# Main_BoardV1.net
KiCad netlist of a schematic drawn in EAGLE
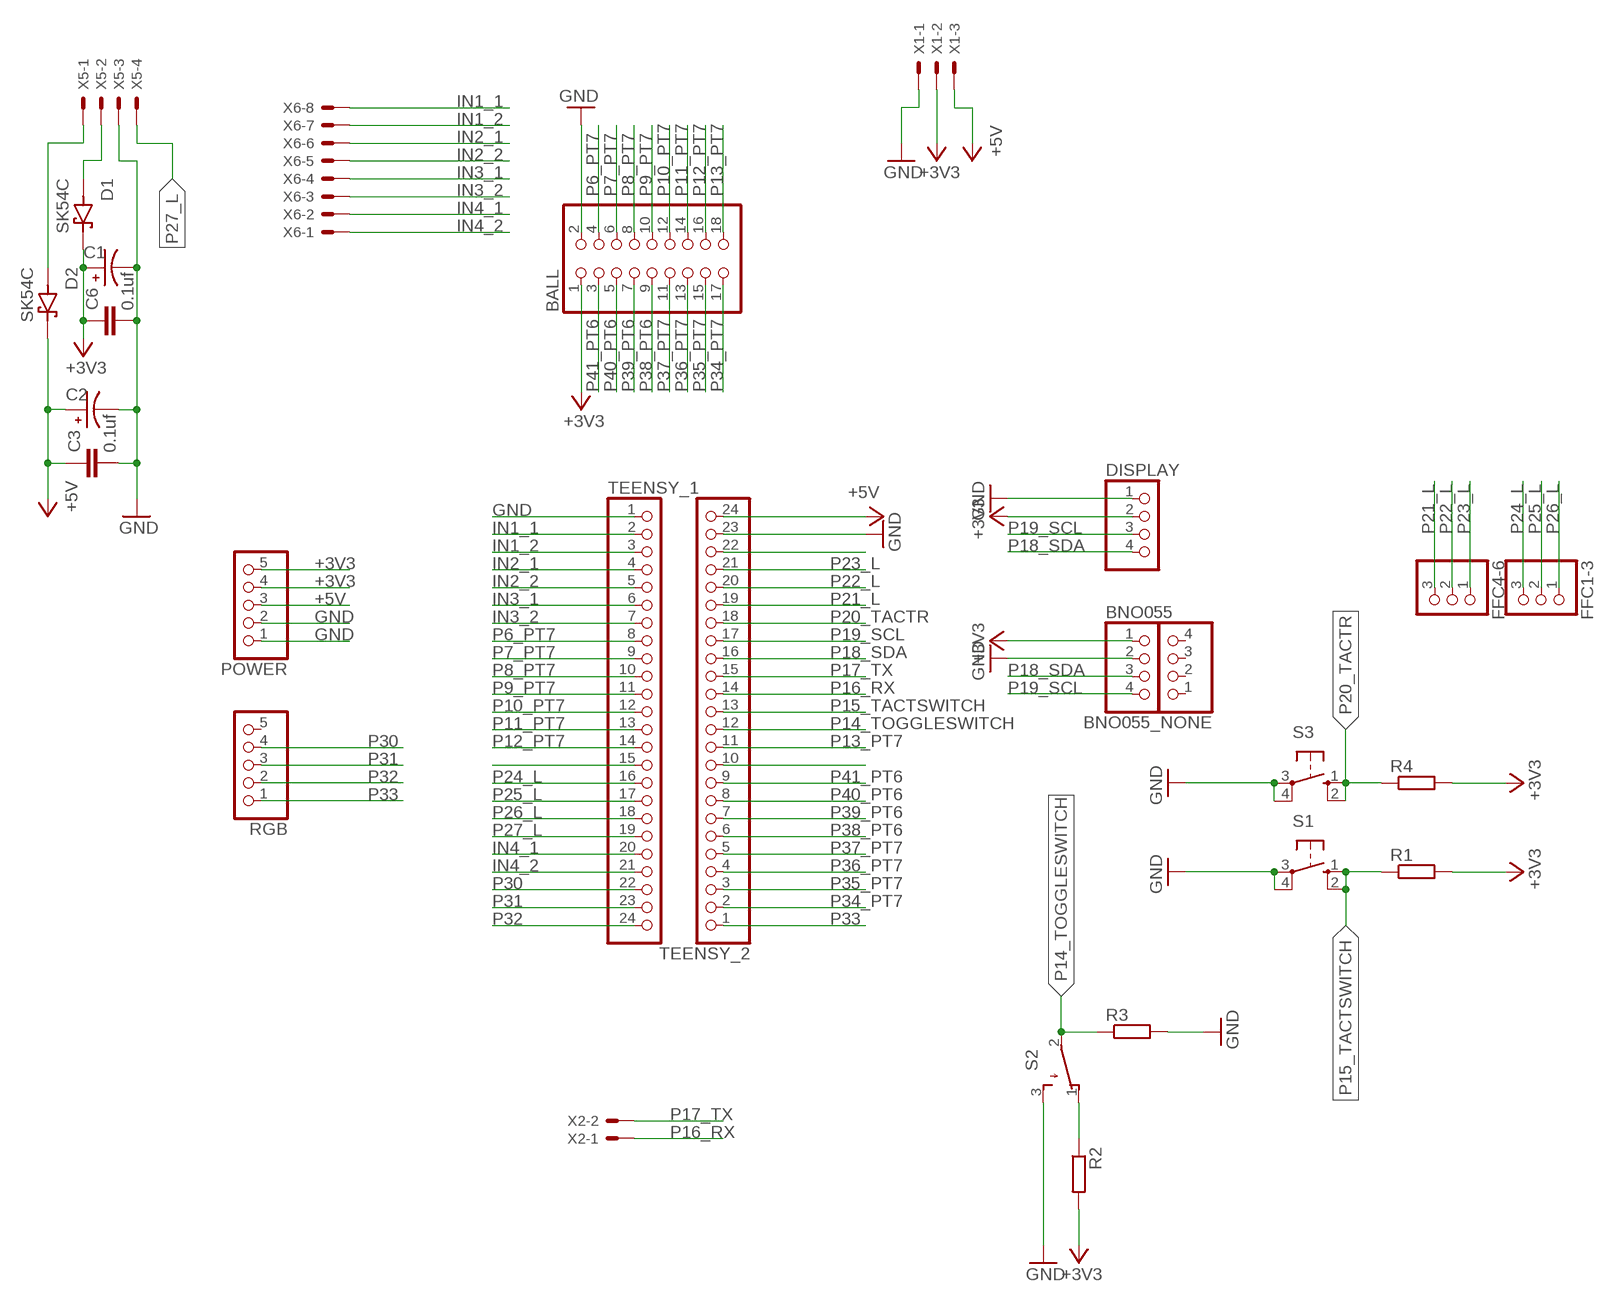
[diagram p0: schematic, sheet 1]

(export (version "E")
  (design (tool "Eeschema 10.0.6"))
  (components
    (comp (ref "BALL")
      (value "PINHD-2X9")
      (footprint "eagle-import:2X09")
      (libsource (lib "eagle-import") (part "PINHD-2X9"))
    )
    (comp (ref "BNO055")
      (value "PINHD-1X4")
      (footprint "eagle-import:1X04")
      (libsource (lib "eagle-import") (part "PINHD-1X4"))
    )
    (comp (ref "BNO055_NONE")
      (value "PINHD-1X4")
      (footprint "eagle-import:1X04")
      (libsource (lib "eagle-import") (part "PINHD-1X4"))
    )
    (comp (ref "C1")
      (value "EEEFK1E332AM")
      (footprint "eagle-import:CAP_EEEFK1E332AM")
      (fields (field (name "MF") "Panasonic"))
      (libsource (lib "eagle-import") (part "EEEFK1E332AM"))
    )
    (comp (ref "C2")
      (value "EEEFK1E332AM")
      (footprint "eagle-import:CAP_EEEFK1E332AM")
      (fields (field (name "MF") "Panasonic"))
      (libsource (lib "eagle-import") (part "EEEFK1E332AM"))
    )
    (comp (ref "C3")
      (value "0.1uf")
      (footprint "eagle-import:C0603")
      (libsource (lib "eagle-import") (part "C-EUC0603"))
    )
    (comp (ref "C6")
      (value "0.1uf")
      (footprint "eagle-import:C0603")
      (libsource (lib "eagle-import") (part "C-EUC0603"))
    )
    (comp (ref "D1")
      (value "SK54C")
      (footprint "eagle-import:DIOM6859X262N")
      (fields (field (name "MF") "Taiwan Semiconductor"))
      (libsource (lib "eagle-import") (part "SK54C"))
    )
    (comp (ref "D2")
      (value "SK54C")
      (footprint "eagle-import:DIOM6859X262N")
      (fields (field (name "MF") "Taiwan Semiconductor"))
      (libsource (lib "eagle-import") (part "SK54C"))
    )
    (comp (ref "DISPLAY")
      (value "PINHD-1X04_2.54-S")
      (footprint "eagle-import:1X04-S")
      (libsource (lib "eagle-import") (part "PINHD-1X04_2.54-S"))
    )
    (comp (ref "FFC1-3")
      (value "PINHD-1X03_2.54-S")
      (footprint "eagle-import:1X03-S")
      (libsource (lib "eagle-import") (part "PINHD-1X03_2.54-S"))
    )
    (comp (ref "FFC4-6")
      (value "PINHD-1X03_2.54-S")
      (footprint "eagle-import:1X03-S")
      (libsource (lib "eagle-import") (part "PINHD-1X03_2.54-S"))
    )
    (comp (ref "POWER")
      (value "PINHD-1X05_2.54-S")
      (footprint "eagle-import:1X05-S")
      (libsource (lib "eagle-import") (part "PINHD-1X05_2.54-S"))
    )
    (comp (ref "R1")
      (value "R-EU_0207/10")
      (footprint "eagle-import:0207_10")
      (libsource (lib "eagle-import") (part "R-EU_0207/10"))
    )
    (comp (ref "R2")
      (value "R-EU_0207/10")
      (footprint "eagle-import:0207_10")
      (libsource (lib "eagle-import") (part "R-EU_0207/10"))
    )
    (comp (ref "R3")
      (value "R-EU_0207/10")
      (footprint "eagle-import:0207_10")
      (libsource (lib "eagle-import") (part "R-EU_0207/10"))
    )
    (comp (ref "R4")
      (value "R-EU_0207/10")
      (footprint "eagle-import:0207_10")
      (libsource (lib "eagle-import") (part "R-EU_0207/10"))
    )
    (comp (ref "RGB")
      (value "PINHD-1X05_2.54-S")
      (footprint "eagle-import:1X05-S")
      (libsource (lib "eagle-import") (part "PINHD-1X05_2.54-S"))
    )
    (comp (ref "S1")
      (value "40-XX")
      (footprint "eagle-import:B3F-40XX")
      (fields (field (name "MF") "OMRON COMPONENTS USA") (field (name "MPN") "B3F-4000"))
      (libsource (lib "eagle-import") (part "40-XX"))
    )
    (comp (ref "S2")
      (value "TL32PO")
      (footprint "eagle-import:TL3XPO")
      (libsource (lib "eagle-import") (part "TL32PO"))
    )
    (comp (ref "S3")
      (value "10-XX")
      (footprint "eagle-import:B3F-10XX")
      (fields (field (name "MPN") "B3F-1000"))
      (libsource (lib "eagle-import") (part "10-XX"))
    )
    (comp (ref "TEENSY_1")
      (value "PINHD-1X24")
      (footprint "eagle-import:1X24")
      (libsource (lib "eagle-import") (part "PINHD-1X24"))
    )
    (comp (ref "TEENSY_2")
      (value "PINHD-1X24")
      (footprint "eagle-import:1X24")
      (libsource (lib "eagle-import") (part "PINHD-1X24"))
    )
    (comp (ref "X1")
      (value "JST-XH-03-PIN-ROUND-PAD")
      (footprint "eagle-import:JST-XH-03-PACKAGE-ROUND-PAD")
      (libsource (lib "eagle-import") (part "JST-XH-03-PIN-ROUND-PAD"))
    )
    (comp (ref "X2")
      (value "JST-XH-02-PIN-ROUND-PAD")
      (footprint "eagle-import:JST-XH-02-PACKAGE-ROUND-PAD")
      (libsource (lib "eagle-import") (part "JST-XH-02-PIN-ROUND-PAD"))
    )
    (comp (ref "X5")
      (value "JST-XH-04-PIN-ROUND-PAD")
      (footprint "eagle-import:JST-XH-04-PACKAGE-ROUND-PAD")
      (libsource (lib "eagle-import") (part "JST-XH-04-PIN-ROUND-PAD"))
    )
    (comp (ref "X6")
      (value "JST-XH-08-PIN-ROUND-PAD")
      (footprint "eagle-import:JST-XH-08-PACKAGE-ROUND-PAD")
      (libsource (lib "eagle-import") (part "JST-XH-08-PIN-ROUND-PAD"))
    )
  )
  (nets
    (net (code "1") (name "+3V3") (class "Default")
      (node (ref "BALL") (pin "1") (pinfunction "1_1") (pintype "passive"))
      (node (ref "BNO055") (pin "1") (pinfunction "1_1") (pintype "passive"))
      (node (ref "C1") (pin "1") (pinfunction "1_1") (pintype "passive"))
      (node (ref "C6") (pin "1") (pinfunction "1_1") (pintype "passive"))
      (node (ref "D1") (pin "C") (pinfunction "K_C") (pintype "passive"))
      (node (ref "DISPLAY") (pin "2") (pinfunction "2_2") (pintype "passive"))
      (node (ref "POWER") (pin "4") (pinfunction "4_4") (pintype "passive"))
      (node (ref "POWER") (pin "5") (pinfunction "5_5") (pintype "passive"))
      (node (ref "R1") (pin "2") (pinfunction "2_2") (pintype "passive"))
      (node (ref "R2") (pin "2") (pinfunction "2_2") (pintype "passive"))
      (node (ref "R4") (pin "2") (pinfunction "2_2") (pintype "passive"))
      (node (ref "X1") (pin "2") (pinfunction "S_2") (pintype "passive"))
    )
    (net (code "2") (name "+5V") (class "Default")
      (node (ref "C2") (pin "1") (pinfunction "1_1") (pintype "passive"))
      (node (ref "C3") (pin "1") (pinfunction "1_1") (pintype "passive"))
      (node (ref "D2") (pin "C") (pinfunction "K_C") (pintype "passive"))
      (node (ref "POWER") (pin "3") (pinfunction "3_3") (pintype "passive"))
      (node (ref "TEENSY_2") (pin "24") (pinfunction "24_24") (pintype "passive"))
      (node (ref "X1") (pin "3") (pinfunction "S_3") (pintype "passive"))
    )
    (net (code "3") (name "/IN1_1") (class "Default")
      (node (ref "TEENSY_1") (pin "2") (pinfunction "2_2") (pintype "passive"))
      (node (ref "X6") (pin "8") (pinfunction "S_8") (pintype "passive"))
    )
    (net (code "4") (name "/IN1_2") (class "Default")
      (node (ref "TEENSY_1") (pin "3") (pinfunction "3_3") (pintype "passive"))
      (node (ref "X6") (pin "7") (pinfunction "S_7") (pintype "passive"))
    )
    (net (code "5") (name "/IN2_1") (class "Default")
      (node (ref "TEENSY_1") (pin "4") (pinfunction "4_4") (pintype "passive"))
      (node (ref "X6") (pin "6") (pinfunction "S_6") (pintype "passive"))
    )
    (net (code "6") (name "/IN2_2") (class "Default")
      (node (ref "TEENSY_1") (pin "5") (pinfunction "5_5") (pintype "passive"))
      (node (ref "X6") (pin "5") (pinfunction "S_5") (pintype "passive"))
    )
    (net (code "7") (name "/IN3_1") (class "Default")
      (node (ref "TEENSY_1") (pin "6") (pinfunction "6_6") (pintype "passive"))
      (node (ref "X6") (pin "4") (pinfunction "S_4") (pintype "passive"))
    )
    (net (code "8") (name "/IN3_2") (class "Default")
      (node (ref "TEENSY_1") (pin "7") (pinfunction "7_7") (pintype "passive"))
      (node (ref "X6") (pin "3") (pinfunction "S_3") (pintype "passive"))
    )
    (net (code "9") (name "/IN4_1") (class "Default")
      (node (ref "TEENSY_1") (pin "20") (pinfunction "20_20") (pintype "passive"))
      (node (ref "X6") (pin "2") (pinfunction "S_2") (pintype "passive"))
    )
    (net (code "10") (name "/IN4_2") (class "Default")
      (node (ref "TEENSY_1") (pin "21") (pinfunction "21_21") (pintype "passive"))
      (node (ref "X6") (pin "1") (pinfunction "S_1") (pintype "passive"))
    )
    (net (code "11") (name "/P6_PT7") (class "Default")
      (node (ref "BALL") (pin "4") (pinfunction "4_4") (pintype "passive"))
      (node (ref "TEENSY_1") (pin "8") (pinfunction "8_8") (pintype "passive"))
    )
    (net (code "12") (name "/P7_PT7") (class "Default")
      (node (ref "BALL") (pin "6") (pinfunction "6_6") (pintype "passive"))
      (node (ref "TEENSY_1") (pin "9") (pinfunction "9_9") (pintype "passive"))
    )
    (net (code "13") (name "/P8_PT7") (class "Default")
      (node (ref "BALL") (pin "8") (pinfunction "8_8") (pintype "passive"))
      (node (ref "TEENSY_1") (pin "10") (pinfunction "10_10") (pintype "passive"))
    )
    (net (code "14") (name "/P9_PT7") (class "Default")
      (node (ref "BALL") (pin "10") (pinfunction "10_10") (pintype "passive"))
      (node (ref "TEENSY_1") (pin "11") (pinfunction "11_11") (pintype "passive"))
    )
    (net (code "15") (name "/P10_PT7") (class "Default")
      (node (ref "BALL") (pin "12") (pinfunction "12_12") (pintype "passive"))
      (node (ref "TEENSY_1") (pin "12") (pinfunction "12_12") (pintype "passive"))
    )
    (net (code "16") (name "/P11_PT7") (class "Default")
      (node (ref "BALL") (pin "14") (pinfunction "14_14") (pintype "passive"))
      (node (ref "TEENSY_1") (pin "13") (pinfunction "13_13") (pintype "passive"))
    )
    (net (code "17") (name "/P12_PT7") (class "Default")
      (node (ref "BALL") (pin "16") (pinfunction "16_16") (pintype "passive"))
      (node (ref "TEENSY_1") (pin "14") (pinfunction "14_14") (pintype "passive"))
    )
    (net (code "18") (name "/P13_PT7") (class "Default")
      (node (ref "BALL") (pin "18") (pinfunction "18_18") (pintype "passive"))
      (node (ref "TEENSY_2") (pin "11") (pinfunction "11_11") (pintype "passive"))
    )
    (net (code "19") (name "/P16_RX") (class "Default")
      (node (ref "TEENSY_2") (pin "14") (pinfunction "14_14") (pintype "passive"))
      (node (ref "X2") (pin "1") (pinfunction "S_1") (pintype "passive"))
    )
    (net (code "20") (name "/P17_TX") (class "Default")
      (node (ref "TEENSY_2") (pin "15") (pinfunction "15_15") (pintype "passive"))
      (node (ref "X2") (pin "2") (pinfunction "S_2") (pintype "passive"))
    )
    (net (code "21") (name "/P18_SDA") (class "Default")
      (node (ref "BNO055") (pin "3") (pinfunction "3_3") (pintype "passive"))
      (node (ref "DISPLAY") (pin "4") (pinfunction "4_4") (pintype "passive"))
      (node (ref "TEENSY_2") (pin "16") (pinfunction "16_16") (pintype "passive"))
    )
    (net (code "22") (name "/P19_SCL") (class "Default")
      (node (ref "BNO055") (pin "4") (pinfunction "4_4") (pintype "passive"))
      (node (ref "DISPLAY") (pin "3") (pinfunction "3_3") (pintype "passive"))
      (node (ref "TEENSY_2") (pin "17") (pinfunction "17_17") (pintype "passive"))
    )
    (net (code "23") (name "/P21_L") (class "Default")
      (node (ref "FFC4-6") (pin "3") (pinfunction "3_3") (pintype "passive"))
      (node (ref "TEENSY_2") (pin "19") (pinfunction "19_19") (pintype "passive"))
    )
    (net (code "24") (name "/P22_L") (class "Default")
      (node (ref "FFC4-6") (pin "2") (pinfunction "2_2") (pintype "passive"))
      (node (ref "TEENSY_2") (pin "20") (pinfunction "20_20") (pintype "passive"))
    )
    (net (code "25") (name "/P23_L") (class "Default")
      (node (ref "FFC4-6") (pin "1") (pinfunction "1_1") (pintype "passive"))
      (node (ref "TEENSY_2") (pin "21") (pinfunction "21_21") (pintype "passive"))
    )
    (net (code "26") (name "/P24_L") (class "Default")
      (node (ref "FFC1-3") (pin "3") (pinfunction "3_3") (pintype "passive"))
      (node (ref "TEENSY_1") (pin "16") (pinfunction "16_16") (pintype "passive"))
    )
    (net (code "27") (name "/P25_L") (class "Default")
      (node (ref "FFC1-3") (pin "2") (pinfunction "2_2") (pintype "passive"))
      (node (ref "TEENSY_1") (pin "17") (pinfunction "17_17") (pintype "passive"))
    )
    (net (code "28") (name "/P26_L") (class "Default")
      (node (ref "FFC1-3") (pin "1") (pinfunction "1_1") (pintype "passive"))
      (node (ref "TEENSY_1") (pin "18") (pinfunction "18_18") (pintype "passive"))
    )
    (net (code "29") (name "/P30") (class "Default")
      (node (ref "RGB") (pin "4") (pinfunction "4_4") (pintype "passive"))
      (node (ref "TEENSY_1") (pin "22") (pinfunction "22_22") (pintype "passive"))
    )
    (net (code "30") (name "/P31") (class "Default")
      (node (ref "RGB") (pin "3") (pinfunction "3_3") (pintype "passive"))
      (node (ref "TEENSY_1") (pin "23") (pinfunction "23_23") (pintype "passive"))
    )
    (net (code "31") (name "/P32") (class "Default")
      (node (ref "RGB") (pin "2") (pinfunction "2_2") (pintype "passive"))
      (node (ref "TEENSY_1") (pin "24") (pinfunction "24_24") (pintype "passive"))
    )
    (net (code "32") (name "/P33") (class "Default")
      (node (ref "RGB") (pin "1") (pinfunction "1_1") (pintype "passive"))
      (node (ref "TEENSY_2") (pin "1") (pinfunction "1_1") (pintype "passive"))
    )
    (net (code "33") (name "/P34_PT7") (class "Default")
      (node (ref "BALL") (pin "17") (pinfunction "17_17") (pintype "passive"))
      (node (ref "TEENSY_2") (pin "2") (pinfunction "2_2") (pintype "passive"))
    )
    (net (code "34") (name "/P35_PT7") (class "Default")
      (node (ref "BALL") (pin "15") (pinfunction "15_15") (pintype "passive"))
      (node (ref "TEENSY_2") (pin "3") (pinfunction "3_3") (pintype "passive"))
    )
    (net (code "35") (name "/P36_PT7") (class "Default")
      (node (ref "BALL") (pin "13") (pinfunction "13_13") (pintype "passive"))
      (node (ref "TEENSY_2") (pin "4") (pinfunction "4_4") (pintype "passive"))
    )
    (net (code "36") (name "/P37_PT7") (class "Default")
      (node (ref "BALL") (pin "11") (pinfunction "11_11") (pintype "passive"))
      (node (ref "TEENSY_2") (pin "5") (pinfunction "5_5") (pintype "passive"))
    )
    (net (code "37") (name "/P38_PT6") (class "Default")
      (node (ref "BALL") (pin "9") (pinfunction "9_9") (pintype "passive"))
      (node (ref "TEENSY_2") (pin "6") (pinfunction "6_6") (pintype "passive"))
    )
    (net (code "38") (name "/P39_PT6") (class "Default")
      (node (ref "BALL") (pin "7") (pinfunction "7_7") (pintype "passive"))
      (node (ref "TEENSY_2") (pin "7") (pinfunction "7_7") (pintype "passive"))
    )
    (net (code "39") (name "/P40_PT6") (class "Default")
      (node (ref "BALL") (pin "5") (pinfunction "5_5") (pintype "passive"))
      (node (ref "TEENSY_2") (pin "8") (pinfunction "8_8") (pintype "passive"))
    )
    (net (code "40") (name "/P41_PT6") (class "Default")
      (node (ref "BALL") (pin "3") (pinfunction "3_3") (pintype "passive"))
      (node (ref "TEENSY_2") (pin "9") (pinfunction "9_9") (pintype "passive"))
    )
    (net (code "41") (name "GND") (class "Default")
      (node (ref "BALL") (pin "2") (pinfunction "2_2") (pintype "passive"))
      (node (ref "BNO055") (pin "2") (pinfunction "2_2") (pintype "passive"))
      (node (ref "C1") (pin "2") (pinfunction "2_2") (pintype "passive"))
      (node (ref "C2") (pin "2") (pinfunction "2_2") (pintype "passive"))
      (node (ref "C3") (pin "2") (pinfunction "2_2") (pintype "passive"))
      (node (ref "C6") (pin "2") (pinfunction "2_2") (pintype "passive"))
      (node (ref "DISPLAY") (pin "1") (pinfunction "1_1") (pintype "passive"))
      (node (ref "POWER") (pin "1") (pinfunction "1_1") (pintype "passive"))
      (node (ref "POWER") (pin "2") (pinfunction "2_2") (pintype "passive"))
      (node (ref "R3") (pin "2") (pinfunction "2_2") (pintype "passive"))
      (node (ref "S1") (pin "3") (pinfunction "P_3") (pintype "passive"))
      (node (ref "S1") (pin "4") (pinfunction "P1_4") (pintype "passive"))
      (node (ref "S2") (pin "3") (pinfunction "S_3") (pintype "passive"))
      (node (ref "S3") (pin "3") (pinfunction "P_3") (pintype "passive"))
      (node (ref "S3") (pin "4") (pinfunction "P1_4") (pintype "passive"))
      (node (ref "TEENSY_1") (pin "1") (pinfunction "1_1") (pintype "passive"))
      (node (ref "TEENSY_2") (pin "23") (pinfunction "23_23") (pintype "passive"))
      (node (ref "X1") (pin "1") (pinfunction "S_1") (pintype "passive"))
      (node (ref "X5") (pin "3") (pinfunction "S_3") (pintype "passive"))
    )
    (net (code "42") (name "Net-(S2-O)") (class "Default")
      (node (ref "R2") (pin "1") (pinfunction "1_1") (pintype "passive"))
      (node (ref "S2") (pin "1") (pinfunction "O_1") (pintype "passive"))
    )
    (net (code "43") (name "Net-(X5A-S)") (class "Default")
      (node (ref "D2") (pin "A") (pinfunction "A_A") (pintype "passive"))
      (node (ref "X5") (pin "1") (pinfunction "S_1") (pintype "passive"))
    )
    (net (code "44") (name "Net-(X5B-S)") (class "Default")
      (node (ref "D1") (pin "A") (pinfunction "A_A") (pintype "passive"))
      (node (ref "X5") (pin "2") (pinfunction "S_2") (pintype "passive"))
    )
    (net (code "45") (name "P14_TOGGLESWITCH") (class "Default")
      (node (ref "R3") (pin "1") (pinfunction "1_1") (pintype "passive"))
      (node (ref "S2") (pin "2") (pinfunction "P_2") (pintype "passive"))
      (node (ref "TEENSY_2") (pin "12") (pinfunction "12_12") (pintype "passive"))
    )
    (net (code "46") (name "P15_TACTSWITCH") (class "Default")
      (node (ref "R1") (pin "1") (pinfunction "1_1") (pintype "passive"))
      (node (ref "S1") (pin "1") (pinfunction "S_1") (pintype "passive"))
      (node (ref "S1") (pin "2") (pinfunction "S1_2") (pintype "passive"))
      (node (ref "TEENSY_2") (pin "13") (pinfunction "13_13") (pintype "passive"))
    )
    (net (code "47") (name "P20_TACTR") (class "Default")
      (node (ref "R4") (pin "1") (pinfunction "1_1") (pintype "passive"))
      (node (ref "S3") (pin "1") (pinfunction "S_1") (pintype "passive"))
      (node (ref "S3") (pin "2") (pinfunction "S1_2") (pintype "passive"))
      (node (ref "TEENSY_2") (pin "18") (pinfunction "18_18") (pintype "passive"))
    )
    (net (code "48") (name "P27_L") (class "Default")
      (node (ref "TEENSY_1") (pin "19") (pinfunction "19_19") (pintype "passive"))
      (node (ref "X5") (pin "4") (pinfunction "S_4") (pintype "passive"))
    )
    (net (code "49") (name "unconnected-(BNO055_NONE-Pad1)") (class "Default")
      (node (ref "BNO055_NONE") (pin "1") (pinfunction "1_1") (pintype "passive"))
    )
    (net (code "50") (name "unconnected-(BNO055_NONE-Pad2)") (class "Default")
      (node (ref "BNO055_NONE") (pin "2") (pinfunction "2_2") (pintype "passive"))
    )
    (net (code "51") (name "unconnected-(BNO055_NONE-Pad3)") (class "Default")
      (node (ref "BNO055_NONE") (pin "3") (pinfunction "3_3") (pintype "passive"))
    )
    (net (code "52") (name "unconnected-(BNO055_NONE-Pad4)") (class "Default")
      (node (ref "BNO055_NONE") (pin "4") (pinfunction "4_4") (pintype "passive"))
    )
    (net (code "53") (name "unconnected-(RGB-Pad5)") (class "Default")
      (node (ref "RGB") (pin "5") (pinfunction "5_5") (pintype "passive"))
    )
    (net (code "54") (name "unconnected-(TEENSY_1-Pad15)") (class "Default")
      (node (ref "TEENSY_1") (pin "15") (pinfunction "15_15") (pintype "passive"))
    )
    (net (code "55") (name "unconnected-(TEENSY_2-Pad10)") (class "Default")
      (node (ref "TEENSY_2") (pin "10") (pinfunction "10_10") (pintype "passive"))
    )
    (net (code "56") (name "unconnected-(TEENSY_2-Pad22)") (class "Default")
      (node (ref "TEENSY_2") (pin "22") (pinfunction "22_22") (pintype "passive"))
    )
  )
)
